# rev1.net
KiCad netlist of a schematic drawn in EAGLE
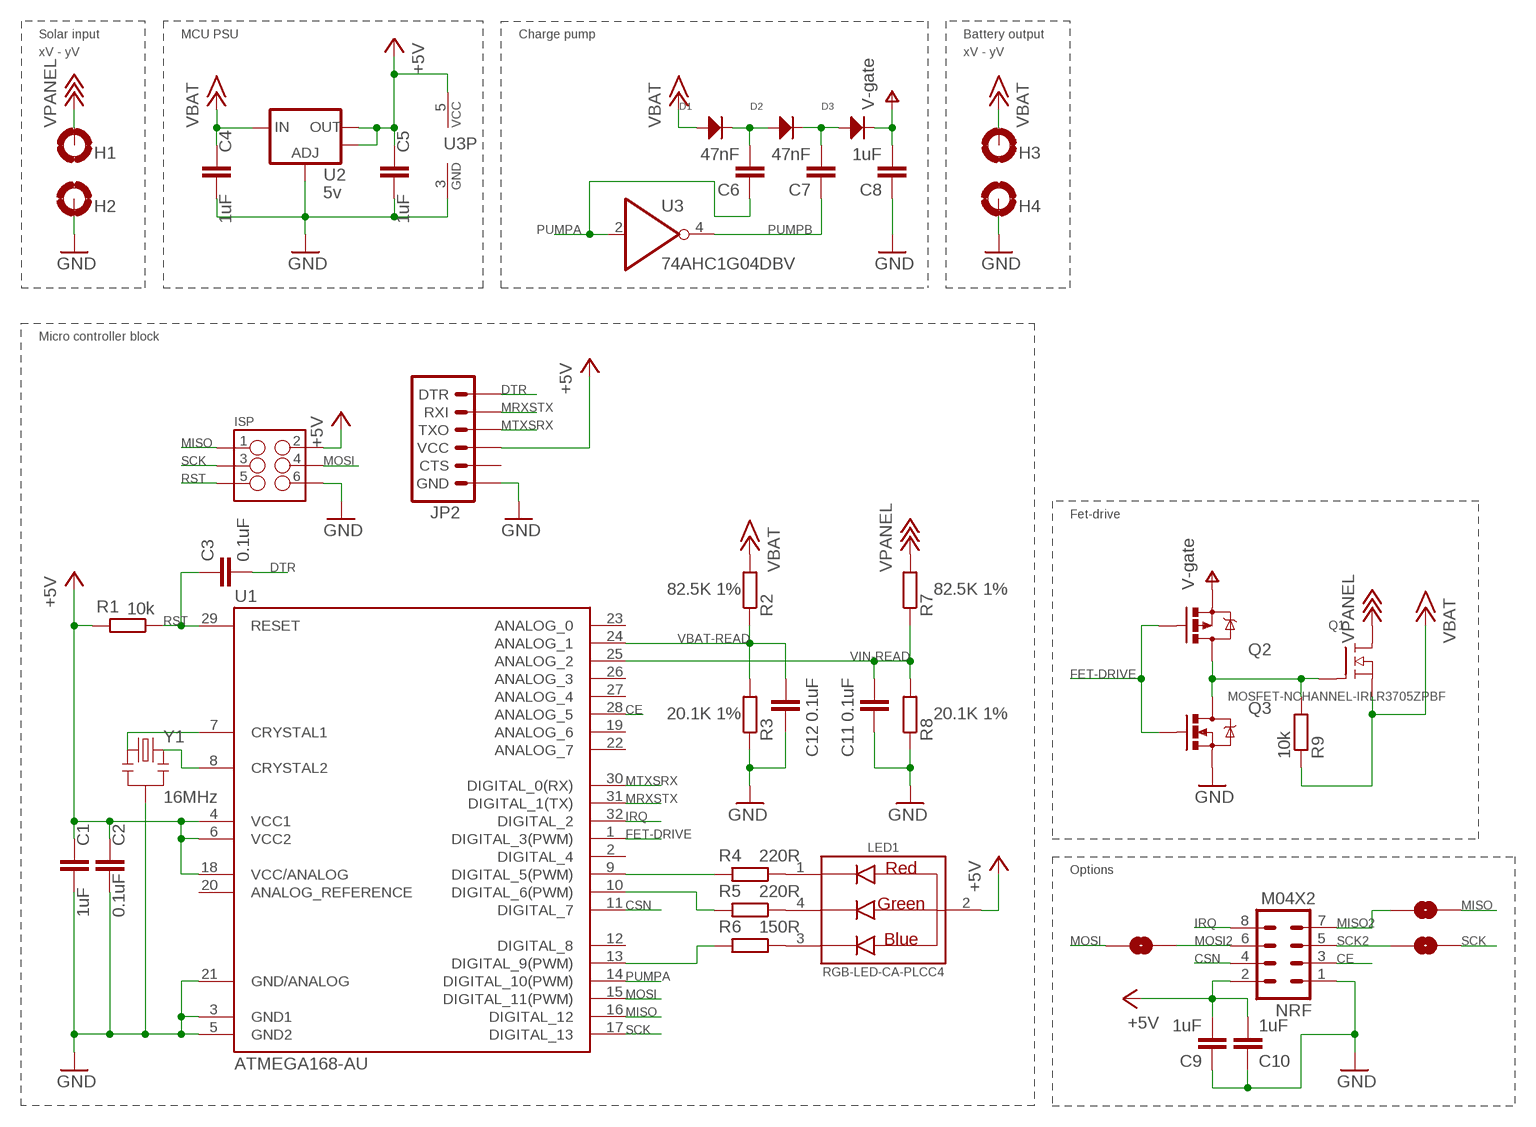
[diagram p0: schematic, sheet 1]

(export (version "E")
  (design (tool "Eeschema 10.0.6"))
  (components
    (comp (ref "C1")
      (value "1uF")
      (footprint "eagle-import:C0603K")
      (libsource (lib "eagle-import") (part "C-EUC0603K"))
    )
    (comp (ref "C2")
      (value "0.1uF")
      (footprint "eagle-import:C0603K")
      (libsource (lib "eagle-import") (part "C-EUC0603K"))
    )
    (comp (ref "C3")
      (value "0.1uF")
      (footprint "eagle-import:C0603K")
      (libsource (lib "eagle-import") (part "C-EUC0603K"))
    )
    (comp (ref "C4")
      (value "1uF")
      (footprint "eagle-import:C0603K")
      (libsource (lib "eagle-import") (part "C-EUC0603K"))
    )
    (comp (ref "C5")
      (value "1uF")
      (footprint "eagle-import:C0603K")
      (libsource (lib "eagle-import") (part "C-EUC0603K"))
    )
    (comp (ref "C6")
      (value "47nF")
      (footprint "eagle-import:C0603K")
      (libsource (lib "eagle-import") (part "C-EUC0603K"))
    )
    (comp (ref "C7")
      (value "47nF")
      (footprint "eagle-import:C0603K")
      (libsource (lib "eagle-import") (part "C-EUC0603K"))
    )
    (comp (ref "C8")
      (value "1uF")
      (footprint "eagle-import:C0603K")
      (libsource (lib "eagle-import") (part "C-EUC0603K"))
    )
    (comp (ref "C9")
      (value "1uF")
      (footprint "eagle-import:C0603K")
      (libsource (lib "eagle-import") (part "C-EUC0603K"))
    )
    (comp (ref "C10")
      (value "1uF")
      (footprint "eagle-import:C0603K")
      (libsource (lib "eagle-import") (part "C-EUC0603K"))
    )
    (comp (ref "C11")
      (value "0.1uF")
      (footprint "eagle-import:C0603K")
      (libsource (lib "eagle-import") (part "C-EUC0603K"))
    )
    (comp (ref "C12")
      (value "0.1uF")
      (footprint "eagle-import:C0603K")
      (libsource (lib "eagle-import") (part "C-EUC0603K"))
    )
    (comp (ref "D1")
      (value "DIODE_SOD-123")
      (footprint "eagle-import:SOD-123")
      (libsource (lib "eagle-import") (part "DIODE_SOD-123"))
    )
    (comp (ref "D2")
      (value "DIODE_SOD-123")
      (footprint "eagle-import:SOD-123")
      (libsource (lib "eagle-import") (part "DIODE_SOD-123"))
    )
    (comp (ref "D3")
      (value "DIODE_SOD-123")
      (footprint "eagle-import:SOD-123")
      (libsource (lib "eagle-import") (part "DIODE_SOD-123"))
    )
    (comp (ref "H1")
      (value "MOUNT-PAD-ROUND3.0")
      (footprint "eagle-import:3,0-PAD")
      (libsource (lib "eagle-import") (part "MOUNT-PAD-ROUND3.0"))
    )
    (comp (ref "H2")
      (value "MOUNT-PAD-ROUND3.0")
      (footprint "eagle-import:3,0-PAD")
      (libsource (lib "eagle-import") (part "MOUNT-PAD-ROUND3.0"))
    )
    (comp (ref "H3")
      (value "MOUNT-PAD-ROUND3.0")
      (footprint "eagle-import:3,0-PAD")
      (libsource (lib "eagle-import") (part "MOUNT-PAD-ROUND3.0"))
    )
    (comp (ref "H4")
      (value "MOUNT-PAD-ROUND3.0")
      (footprint "eagle-import:3,0-PAD")
      (libsource (lib "eagle-import") (part "MOUNT-PAD-ROUND3.0"))
    )
    (comp (ref "ISP")
      (value "M03X22X3_SILK_SM")
      (footprint "eagle-import:2X3")
      (libsource (lib "eagle-import") (part "M03X22X3_SILK_SM"))
    )
    (comp (ref "JP2")
      (value "ARDUINO_SERIAL_PROGRAMLOCK")
      (footprint "eagle-import:1X06_LOCK")
      (libsource (lib "eagle-import") (part "ARDUINO_SERIAL_PROGRAMLOCK"))
    )
    (comp (ref "LED1")
      (value "RGB-LED-CA-PLCC4")
      (footprint "eagle-import:PLCC4")
      (libsource (lib "eagle-import") (part "RGB-LED-CA-PLCC4"))
    )
    (comp (ref "NRF")
      (value "M04X2")
      (footprint "eagle-import:2X4")
      (libsource (lib "eagle-import") (part "M04X2"))
    )
    (comp (ref "Q1")
      (value "MOSFET-NCHANNEL-IRLR3705ZPBF")
      (footprint "eagle-import:DPAK")
      (libsource (lib "eagle-import") (part "MOSFET-NCHANNEL-IRLR3705ZPBF"))
    )
    (comp (ref "Q2")
      (value "MOSFET-PCHANNEL")
      (footprint "eagle-import:SOT23")
      (libsource (lib "eagle-import") (part "MOSFET-PCHANNEL"))
    )
    (comp (ref "Q3")
      (value "MOSFET-NCHANNELBSS138")
      (footprint "eagle-import:SOT23")
      (libsource (lib "eagle-import") (part "MOSFET-NCHANNELBSS138"))
    )
    (comp (ref "R1")
      (value "10k")
      (footprint "eagle-import:R0603")
      (libsource (lib "eagle-import") (part "R-EU_R0603"))
    )
    (comp (ref "R2")
      (value "82.5K 1%")
      (footprint "eagle-import:R0603")
      (libsource (lib "eagle-import") (part "R-EU_R0603"))
    )
    (comp (ref "R3")
      (value "20.1K 1%")
      (footprint "eagle-import:R0603")
      (libsource (lib "eagle-import") (part "R-EU_R0603"))
    )
    (comp (ref "R4")
      (value "220R")
      (footprint "eagle-import:R0603")
      (libsource (lib "eagle-import") (part "R-EU_R0603"))
    )
    (comp (ref "R5")
      (value "220R")
      (footprint "eagle-import:R0603")
      (libsource (lib "eagle-import") (part "R-EU_R0603"))
    )
    (comp (ref "R6")
      (value "150R")
      (footprint "eagle-import:R0603")
      (libsource (lib "eagle-import") (part "R-EU_R0603"))
    )
    (comp (ref "R7")
      (value "82.5K 1%")
      (footprint "eagle-import:R0603")
      (libsource (lib "eagle-import") (part "R-EU_R0603"))
    )
    (comp (ref "R8")
      (value "20.1K 1%")
      (footprint "eagle-import:R0603")
      (libsource (lib "eagle-import") (part "R-EU_R0603"))
    )
    (comp (ref "R9")
      (value "10k")
      (footprint "eagle-import:R0603")
      (libsource (lib "eagle-import") (part "R-EU_R0603"))
    )
    (comp (ref "SJ2")
      (value "SOLDERJUMPERNO")
      (footprint "eagle-import:SJ_2S-NO")
      (libsource (lib "eagle-import") (part "SOLDERJUMPERNO"))
    )
    (comp (ref "SJ5")
      (value "SOLDERJUMPERNO")
      (footprint "eagle-import:SJ_2S-NO")
      (libsource (lib "eagle-import") (part "SOLDERJUMPERNO"))
    )
    (comp (ref "SJ6")
      (value "SOLDERJUMPERNO")
      (footprint "eagle-import:SJ_2S-NO")
      (libsource (lib "eagle-import") (part "SOLDERJUMPERNO"))
    )
    (comp (ref "U1")
      (value "ATMEGA168-AU")
      (footprint "eagle-import:TQFP32-08")
      (libsource (lib "eagle-import") (part "ATMEGA168-AU"))
    )
    (comp (ref "U2")
      (value "5v")
      (footprint "eagle-import:SOT223")
      (libsource (lib "eagle-import") (part "V_REG_LM1117SOT223"))
    )
    (comp (ref "U3")
      (value "74AHC1G04DBV")
      (footprint "eagle-import:SOT23-5")
      (libsource (lib "eagle-import") (part "741G04DBVAHC"))
    )
    (comp (ref "Y1")
      (value "16MHz")
      (footprint "eagle-import:RESONATOR-SMD")
      (libsource (lib "eagle-import") (part "RESONATOR16MHZ"))
    )
  )
  (nets
    (net (code "1") (name "+5V") (class "Default")
      (node (ref "C1") (pin "1") (pinfunction "1_1") (pintype "passive"))
      (node (ref "C10") (pin "2") (pinfunction "2_2") (pintype "passive"))
      (node (ref "C2") (pin "1") (pinfunction "1_1") (pintype "passive"))
      (node (ref "C5") (pin "1") (pinfunction "1_1") (pintype "passive"))
      (node (ref "C9") (pin "2") (pinfunction "2_2") (pintype "passive"))
      (node (ref "ISP") (pin "2") (pinfunction "2_2") (pintype "bidirectional"))
      (node (ref "JP2") (pin "4") (pinfunction "VCC_4") (pintype "passive"))
      (node (ref "LED1") (pin "2") (pinfunction "CA_2") (pintype "bidirectional"))
      (node (ref "NRF") (pin "2") (pinfunction "2_2") (pintype "passive"))
      (node (ref "R1") (pin "2") (pinfunction "2_2") (pintype "passive"))
      (node (ref "U1") (pin "18") (pinfunction "VCC/ANALOG_18") (pintype "passive"))
      (node (ref "U1") (pin "4") (pinfunction "VCC1_4") (pintype "power_in"))
      (node (ref "U1") (pin "6") (pinfunction "VCC2_6") (pintype "power_in"))
      (node (ref "U2") (pin "2") (pinfunction "OUT_2") (pintype "output"))
      (node (ref "U2") (pin "4") (pinfunction "OUT_4") (pintype "output"))
      (node (ref "U3") (pin "5") (pinfunction "VCC_5") (pintype "power_in"))
    )
    (net (code "2") (name "/CE") (class "Default")
      (node (ref "NRF") (pin "3") (pinfunction "3_3") (pintype "passive"))
      (node (ref "U1") (pin "28") (pinfunction "ANALOG_5_28") (pintype "bidirectional"))
    )
    (net (code "3") (name "/CSN") (class "Default")
      (node (ref "NRF") (pin "4") (pinfunction "4_4") (pintype "passive"))
      (node (ref "U1") (pin "11") (pinfunction "DIGITAL_7_11") (pintype "bidirectional"))
    )
    (net (code "4") (name "/DTR") (class "Default")
      (node (ref "C3") (pin "2") (pinfunction "2_2") (pintype "passive"))
      (node (ref "JP2") (pin "1") (pinfunction "DTR_1") (pintype "passive"))
    )
    (net (code "5") (name "/FET-DRIVE") (class "Default")
      (node (ref "Q2") (pin "1") (pinfunction "G_1") (pintype "passive"))
      (node (ref "Q3") (pin "1") (pinfunction "G_1") (pintype "passive"))
      (node (ref "U1") (pin "1") (pinfunction "DIGITAL_3(PWM)_1") (pintype "bidirectional"))
    )
    (net (code "6") (name "/IRQ") (class "Default")
      (node (ref "NRF") (pin "8") (pinfunction "8_8") (pintype "passive"))
      (node (ref "U1") (pin "32") (pinfunction "DIGITAL_2_32") (pintype "bidirectional"))
    )
    (net (code "7") (name "/MISO") (class "Default")
      (node (ref "ISP") (pin "1") (pinfunction "1_1") (pintype "bidirectional"))
      (node (ref "SJ6") (pin "2") (pinfunction "2_2") (pintype "passive"))
      (node (ref "U1") (pin "16") (pinfunction "DIGITAL_12_16") (pintype "bidirectional"))
    )
    (net (code "8") (name "/MISO2") (class "Default")
      (node (ref "NRF") (pin "7") (pinfunction "7_7") (pintype "passive"))
      (node (ref "SJ6") (pin "1") (pinfunction "1_1") (pintype "passive"))
    )
    (net (code "9") (name "/MOSI") (class "Default")
      (node (ref "ISP") (pin "4") (pinfunction "4_4") (pintype "bidirectional"))
      (node (ref "SJ2") (pin "1") (pinfunction "1_1") (pintype "passive"))
      (node (ref "U1") (pin "15") (pinfunction "DIGITAL_11(PWM)_15") (pintype "bidirectional"))
    )
    (net (code "10") (name "/MOSI2") (class "Default")
      (node (ref "NRF") (pin "6") (pinfunction "6_6") (pintype "passive"))
      (node (ref "SJ2") (pin "2") (pinfunction "2_2") (pintype "passive"))
    )
    (net (code "11") (name "/MRXSTX") (class "Default")
      (node (ref "JP2") (pin "2") (pinfunction "RXI_2") (pintype "passive"))
      (node (ref "U1") (pin "31") (pinfunction "DIGITAL_1(TX)_31") (pintype "bidirectional"))
    )
    (net (code "12") (name "/MTXSRX") (class "Default")
      (node (ref "JP2") (pin "3") (pinfunction "TXO_3") (pintype "passive"))
      (node (ref "U1") (pin "30") (pinfunction "DIGITAL_0(RX)_30") (pintype "bidirectional"))
    )
    (net (code "13") (name "/PUMPA") (class "Default")
      (node (ref "C6") (pin "1") (pinfunction "1_1") (pintype "passive"))
      (node (ref "U1") (pin "14") (pinfunction "DIGITAL_10(PWM)_14") (pintype "bidirectional"))
      (node (ref "U3") (pin "2") (pinfunction "I_2") (pintype "input"))
    )
    (net (code "14") (name "/PUMPB") (class "Default")
      (node (ref "C7") (pin "1") (pinfunction "1_1") (pintype "passive"))
      (node (ref "U3") (pin "4") (pinfunction "O_4") (pintype "output"))
    )
    (net (code "15") (name "/RST") (class "Default")
      (node (ref "C3") (pin "1") (pinfunction "1_1") (pintype "passive"))
      (node (ref "ISP") (pin "5") (pinfunction "5_5") (pintype "bidirectional"))
      (node (ref "R1") (pin "1") (pinfunction "1_1") (pintype "passive"))
      (node (ref "U1") (pin "29") (pinfunction "RESET_29") (pintype "bidirectional"))
    )
    (net (code "16") (name "/SCK") (class "Default")
      (node (ref "ISP") (pin "3") (pinfunction "3_3") (pintype "bidirectional"))
      (node (ref "SJ5") (pin "2") (pinfunction "2_2") (pintype "passive"))
      (node (ref "U1") (pin "17") (pinfunction "DIGITAL_13_17") (pintype "bidirectional"))
    )
    (net (code "17") (name "/SCK2") (class "Default")
      (node (ref "NRF") (pin "5") (pinfunction "5_5") (pintype "passive"))
      (node (ref "SJ5") (pin "1") (pinfunction "1_1") (pintype "passive"))
    )
    (net (code "18") (name "/VBAT-READ") (class "Default")
      (node (ref "C12") (pin "2") (pinfunction "2_2") (pintype "passive"))
      (node (ref "R2") (pin "1") (pinfunction "1_1") (pintype "passive"))
      (node (ref "R3") (pin "2") (pinfunction "2_2") (pintype "passive"))
      (node (ref "U1") (pin "24") (pinfunction "ANALOG_1_24") (pintype "bidirectional"))
    )
    (net (code "19") (name "/VIN-READ") (class "Default")
      (node (ref "C11") (pin "2") (pinfunction "2_2") (pintype "passive"))
      (node (ref "R7") (pin "1") (pinfunction "1_1") (pintype "passive"))
      (node (ref "R8") (pin "2") (pinfunction "2_2") (pintype "passive"))
      (node (ref "U1") (pin "25") (pinfunction "ANALOG_2_25") (pintype "bidirectional"))
    )
    (net (code "20") (name "GND") (class "Default")
      (node (ref "C1") (pin "2") (pinfunction "2_2") (pintype "passive"))
      (node (ref "C10") (pin "1") (pinfunction "1_1") (pintype "passive"))
      (node (ref "C11") (pin "1") (pinfunction "1_1") (pintype "passive"))
      (node (ref "C12") (pin "1") (pinfunction "1_1") (pintype "passive"))
      (node (ref "C2") (pin "2") (pinfunction "2_2") (pintype "passive"))
      (node (ref "C4") (pin "2") (pinfunction "2_2") (pintype "passive"))
      (node (ref "C5") (pin "2") (pinfunction "2_2") (pintype "passive"))
      (node (ref "C8") (pin "1") (pinfunction "1_1") (pintype "passive"))
      (node (ref "C9") (pin "1") (pinfunction "1_1") (pintype "passive"))
      (node (ref "H2") (pin "B3,0") (pinfunction "MOUNT_B3,0") (pintype "passive"))
      (node (ref "H4") (pin "B3,0") (pinfunction "MOUNT_B3,0") (pintype "passive"))
      (node (ref "ISP") (pin "6") (pinfunction "6_6") (pintype "bidirectional"))
      (node (ref "JP2") (pin "6") (pinfunction "GND_6") (pintype "passive"))
      (node (ref "NRF") (pin "1") (pinfunction "1_1") (pintype "passive"))
      (node (ref "Q3") (pin "2") (pinfunction "S_2") (pintype "passive"))
      (node (ref "R3") (pin "1") (pinfunction "1_1") (pintype "passive"))
      (node (ref "R8") (pin "1") (pinfunction "1_1") (pintype "passive"))
      (node (ref "U1") (pin "21") (pinfunction "GND/ANALOG_21") (pintype "power_in"))
      (node (ref "U1") (pin "3") (pinfunction "GND1_3") (pintype "power_in"))
      (node (ref "U1") (pin "5") (pinfunction "GND2_5") (pintype "power_in"))
      (node (ref "U2") (pin "1") (pinfunction "ADJ_1") (pintype "input"))
      (node (ref "U3") (pin "3") (pinfunction "GND_3") (pintype "power_in"))
      (node (ref "Y1") (pin "2") (pinfunction "2_2") (pintype "passive"))
    )
    (net (code "21") (name "Net-(C6-Pad2)") (class "Default")
      (node (ref "C6") (pin "2") (pinfunction "2_2") (pintype "passive"))
      (node (ref "D1") (pin "CATHODE") (pinfunction "CATHODE_CATHODE") (pintype "bidirectional"))
      (node (ref "D2") (pin "ANODE") (pinfunction "ANODE_ANODE") (pintype "bidirectional"))
    )
    (net (code "22") (name "Net-(C7-Pad2)") (class "Default")
      (node (ref "C7") (pin "2") (pinfunction "2_2") (pintype "passive"))
      (node (ref "D2") (pin "CATHODE") (pinfunction "CATHODE_CATHODE") (pintype "bidirectional"))
      (node (ref "D3") (pin "ANODE") (pinfunction "ANODE_ANODE") (pintype "bidirectional"))
    )
    (net (code "23") (name "Net-(LED1-BC)") (class "Default")
      (node (ref "LED1") (pin "3") (pinfunction "BC_3") (pintype "bidirectional"))
      (node (ref "R6") (pin "1") (pinfunction "1_1") (pintype "passive"))
    )
    (net (code "24") (name "Net-(LED1-GC)") (class "Default")
      (node (ref "LED1") (pin "4") (pinfunction "GC_4") (pintype "bidirectional"))
      (node (ref "R5") (pin "1") (pinfunction "1_1") (pintype "passive"))
    )
    (net (code "25") (name "Net-(LED1-RC)") (class "Default")
      (node (ref "LED1") (pin "1") (pinfunction "RC_1") (pintype "bidirectional"))
      (node (ref "R4") (pin "1") (pinfunction "1_1") (pintype "passive"))
    )
    (net (code "26") (name "Net-(Q1-G)") (class "Default")
      (node (ref "Q1") (pin "1") (pinfunction "G_1") (pintype "bidirectional"))
      (node (ref "Q2") (pin "3") (pinfunction "D_3") (pintype "passive"))
      (node (ref "Q3") (pin "3") (pinfunction "D_3") (pintype "passive"))
      (node (ref "R9") (pin "2") (pinfunction "2_2") (pintype "passive"))
    )
    (net (code "27") (name "Net-(U1-CRYSTAL1)") (class "Default")
      (node (ref "U1") (pin "7") (pinfunction "CRYSTAL1_7") (pintype "bidirectional"))
      (node (ref "Y1") (pin "1") (pinfunction "1_1") (pintype "passive"))
    )
    (net (code "28") (name "Net-(U1-CRYSTAL2)") (class "Default")
      (node (ref "U1") (pin "8") (pinfunction "CRYSTAL2_8") (pintype "bidirectional"))
      (node (ref "Y1") (pin "3") (pinfunction "3_3") (pintype "passive"))
    )
    (net (code "29") (name "Net-(U1-DIGITAL_5(PWM))") (class "Default")
      (node (ref "R4") (pin "2") (pinfunction "2_2") (pintype "passive"))
      (node (ref "U1") (pin "9") (pinfunction "DIGITAL_5(PWM)_9") (pintype "bidirectional"))
    )
    (net (code "30") (name "Net-(U1-DIGITAL_6(PWM))") (class "Default")
      (node (ref "R5") (pin "2") (pinfunction "2_2") (pintype "passive"))
      (node (ref "U1") (pin "10") (pinfunction "DIGITAL_6(PWM)_10") (pintype "bidirectional"))
    )
    (net (code "31") (name "Net-(U1-DIGITAL_9(PWM))") (class "Default")
      (node (ref "R6") (pin "2") (pinfunction "2_2") (pintype "passive"))
      (node (ref "U1") (pin "13") (pinfunction "DIGITAL_9(PWM)_13") (pintype "bidirectional"))
    )
    (net (code "32") (name "V-gate") (class "Default")
      (node (ref "C8") (pin "2") (pinfunction "2_2") (pintype "passive"))
      (node (ref "D3") (pin "CATHODE") (pinfunction "CATHODE_CATHODE") (pintype "bidirectional"))
      (node (ref "Q2") (pin "2") (pinfunction "S_2") (pintype "passive"))
    )
    (net (code "33") (name "VBAT") (class "Default")
      (node (ref "C4") (pin "1") (pinfunction "1_1") (pintype "passive"))
      (node (ref "D1") (pin "ANODE") (pinfunction "ANODE_ANODE") (pintype "bidirectional"))
      (node (ref "H3") (pin "B3,0") (pinfunction "MOUNT_B3,0") (pintype "passive"))
      (node (ref "Q1") (pin "2") (pinfunction "S_2") (pintype "bidirectional"))
      (node (ref "R2") (pin "2") (pinfunction "2_2") (pintype "passive"))
      (node (ref "R9") (pin "1") (pinfunction "1_1") (pintype "passive"))
      (node (ref "U2") (pin "3") (pinfunction "IN_3") (pintype "input"))
    )
    (net (code "34") (name "VPANEL") (class "Default")
      (node (ref "H1") (pin "B3,0") (pinfunction "MOUNT_B3,0") (pintype "passive"))
      (node (ref "Q1") (pin "TAB") (pinfunction "D_TAB") (pintype "bidirectional"))
      (node (ref "R7") (pin "2") (pinfunction "2_2") (pintype "passive"))
    )
    (net (code "35") (name "unconnected-(JP2-CTS-Pad5)") (class "Default")
      (node (ref "JP2") (pin "5") (pinfunction "CTS_5") (pintype "passive"))
    )
    (net (code "36") (name "unconnected-(U1-ANALOG_0-Pad23)") (class "Default")
      (node (ref "U1") (pin "23") (pinfunction "ANALOG_0_23") (pintype "bidirectional"))
    )
    (net (code "37") (name "unconnected-(U1-ANALOG_3-Pad26)") (class "Default")
      (node (ref "U1") (pin "26") (pinfunction "ANALOG_3_26") (pintype "bidirectional"))
    )
    (net (code "38") (name "unconnected-(U1-ANALOG_4-Pad27)") (class "Default")
      (node (ref "U1") (pin "27") (pinfunction "ANALOG_4_27") (pintype "bidirectional"))
    )
    (net (code "39") (name "unconnected-(U1-ANALOG_6-Pad19)") (class "Default")
      (node (ref "U1") (pin "19") (pinfunction "ANALOG_6_19") (pintype "passive"))
    )
    (net (code "40") (name "unconnected-(U1-ANALOG_7-Pad22)") (class "Default")
      (node (ref "U1") (pin "22") (pinfunction "ANALOG_7_22") (pintype "passive"))
    )
    (net (code "41") (name "unconnected-(U1-ANALOG_REFERENCE-Pad20)") (class "Default")
      (node (ref "U1") (pin "20") (pinfunction "ANALOG_REFERENCE_20") (pintype "passive"))
    )
    (net (code "42") (name "unconnected-(U1-DIGITAL_4-Pad2)") (class "Default")
      (node (ref "U1") (pin "2") (pinfunction "DIGITAL_4_2") (pintype "bidirectional"))
    )
    (net (code "43") (name "unconnected-(U1-DIGITAL_8-Pad12)") (class "Default")
      (node (ref "U1") (pin "12") (pinfunction "DIGITAL_8_12") (pintype "bidirectional"))
    )
  )
)
